# DA14580.net
KiCad netlist of a schematic drawn in Altium Designer
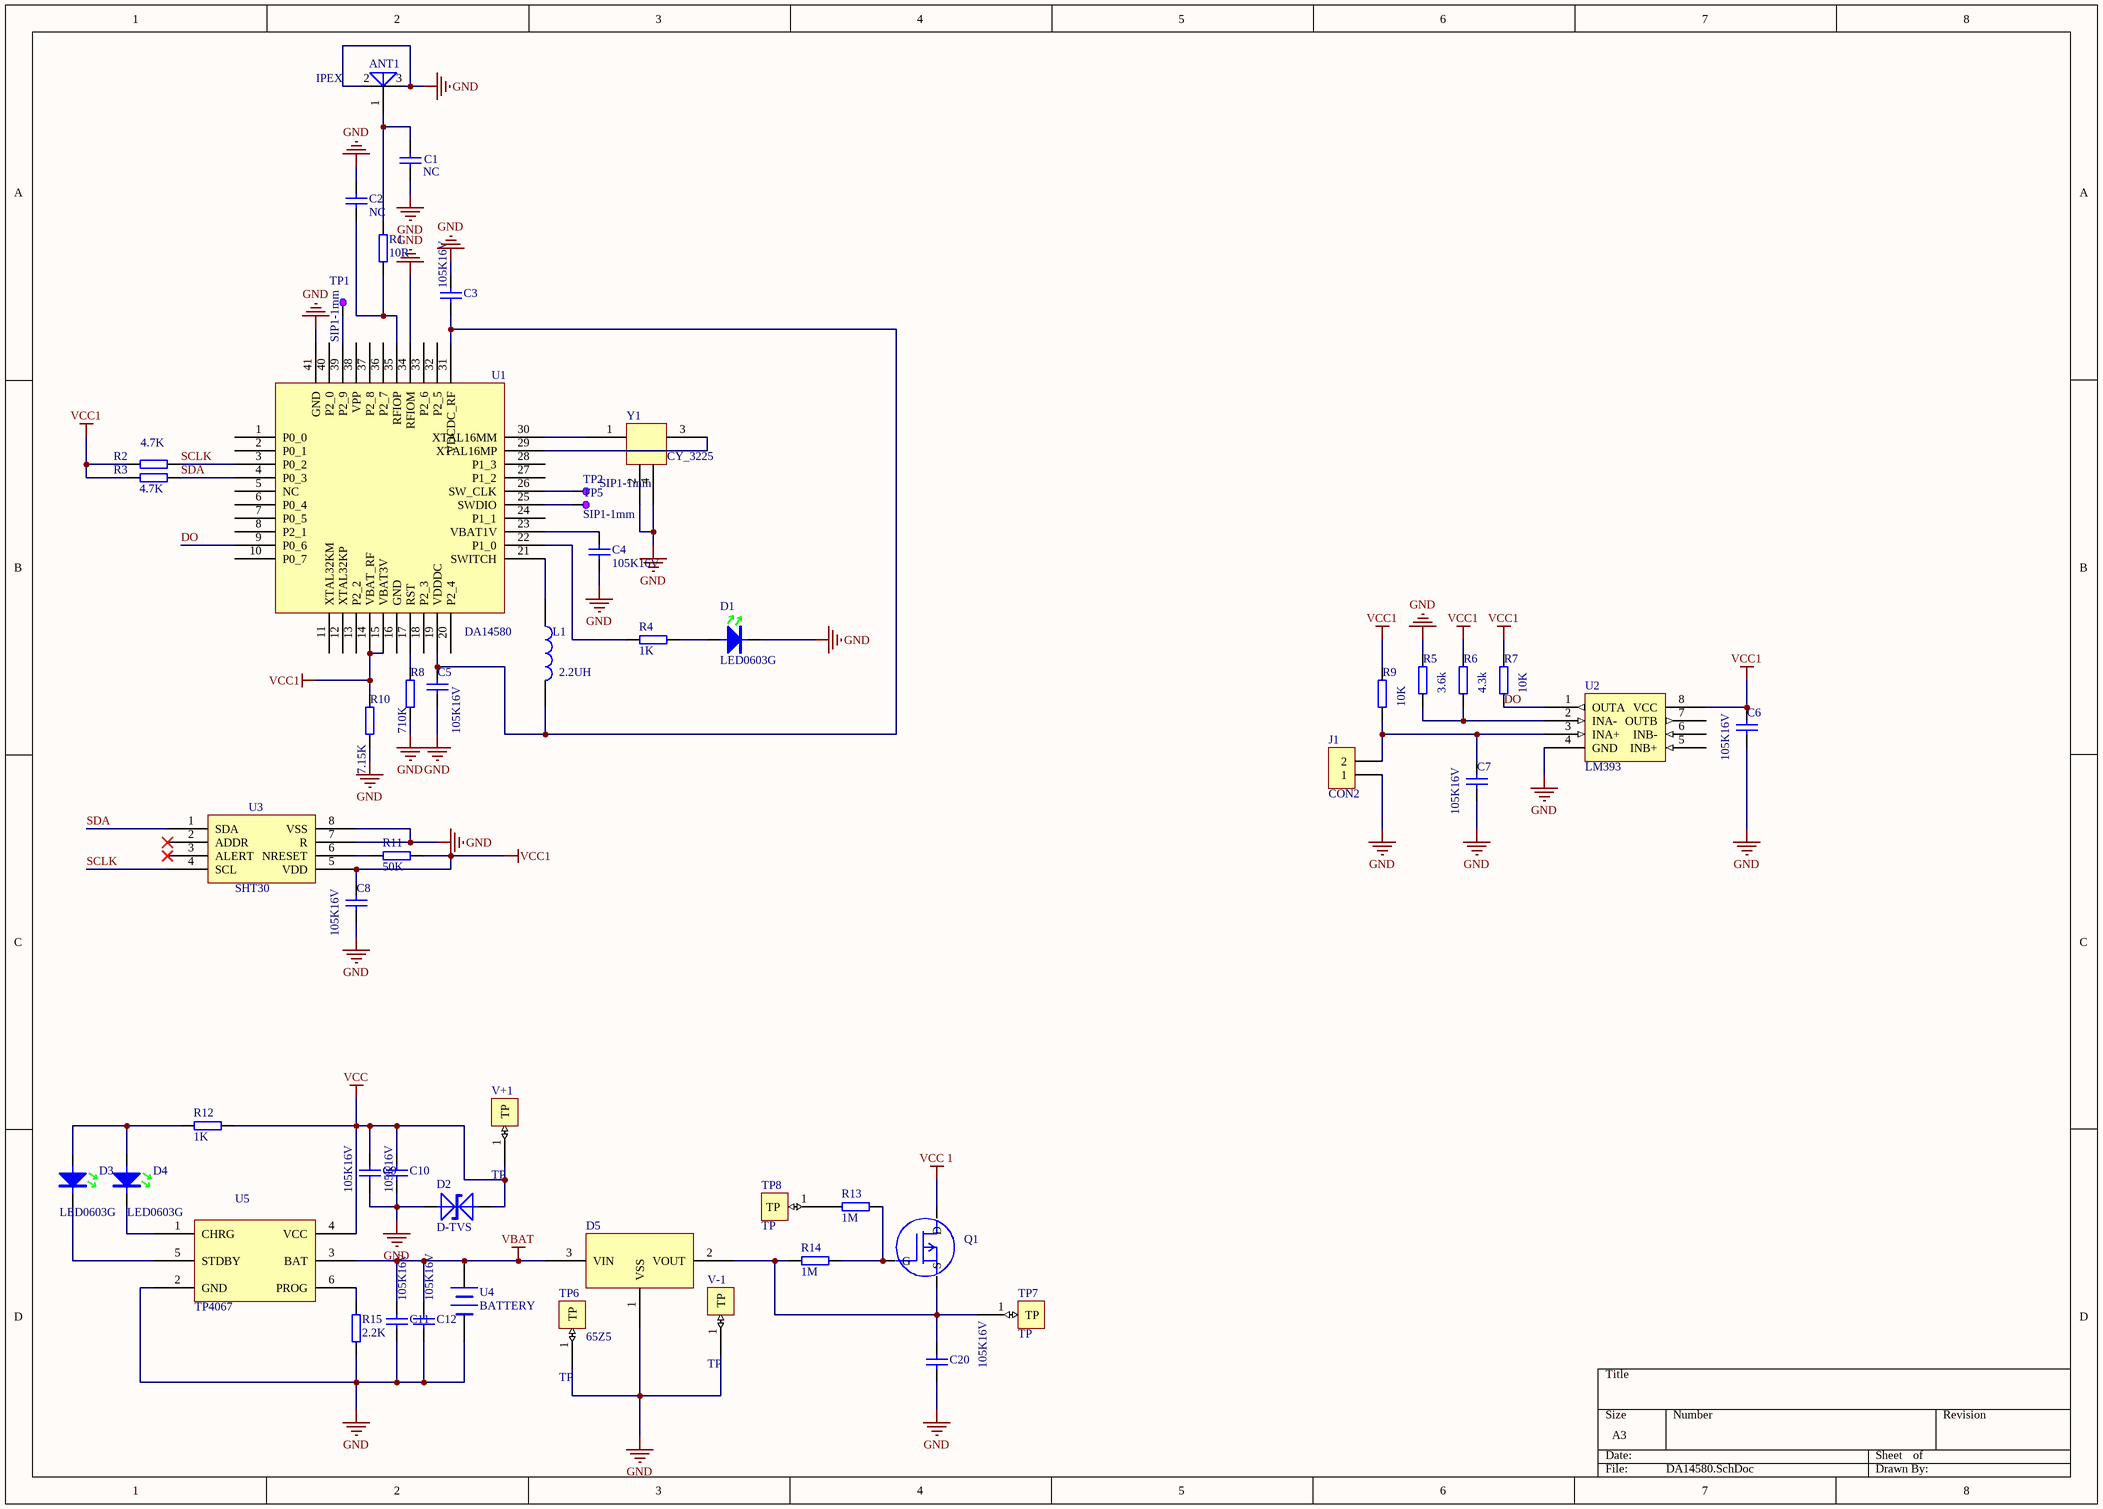
[diagram p0: DA14580.SchDoc]

(export (version "E")
  (design (tool "Eeschema 10.0.6"))
  (components
    (comp (ref "ANT1") (value "IPEX") (footprint "IFA") (libsource (lib "AIWAC-bolsterV01") (part "J-IPEX")))
    (comp (ref "C1")
      (value "NC")
      (footprint "C0402")
      (description "贴片电容-陶瓷")
      (libsource (lib "AIWAC-bolsterV01") (part "C0402X7R-101J10V"))
    )
    (comp (ref "C2")
      (value "NC")
      (footprint "C0402")
      (description "贴片电容-陶瓷")
      (libsource (lib "AIWAC-bolsterV01") (part "C0402X7R-101J10V"))
    )
    (comp (ref "C3")
      (value "105K16V")
      (footprint "C0603")
      (description "贴片电容-陶瓷")
      (libsource (lib "AIWAC-bolsterV01") (part "C0603X7R-105K16V"))
    )
    (comp (ref "C4")
      (value "105K16V")
      (footprint "C0603")
      (description "贴片电容-陶瓷")
      (libsource (lib "AIWAC-bolsterV01") (part "C0603X7R-105K16V"))
    )
    (comp (ref "C5")
      (value "105K16V")
      (footprint "C0603")
      (description "贴片电容-陶瓷")
      (libsource (lib "AIWAC-bolsterV01") (part "C0603X7R-105K16V"))
    )
    (comp (ref "C6")
      (value "105K16V")
      (footprint "C0603")
      (description "贴片电容-陶瓷")
      (libsource (lib "AIWAC-bolsterV01") (part "C0603X7R-105K16V"))
    )
    (comp (ref "C7")
      (value "105K16V")
      (footprint "C0603")
      (description "贴片电容-陶瓷")
      (libsource (lib "AIWAC-bolsterV01") (part "C0603X7R-105K16V"))
    )
    (comp (ref "C8")
      (value "105K16V")
      (footprint "C0603")
      (description "贴片电容-陶瓷")
      (libsource (lib "AIWAC-bolsterV01") (part "C0603X7R-105K16V"))
    )
    (comp (ref "C9")
      (value "105K16V")
      (footprint "C0603")
      (description "贴片电容-陶瓷")
      (libsource (lib "AIWAC-bolsterV01") (part "C0603X7R-105K16V"))
    )
    (comp (ref "C10")
      (value "105K16V")
      (footprint "C0603")
      (description "贴片电容-陶瓷")
      (libsource (lib "AIWAC-bolsterV01") (part "C0603X7R-105K16V"))
    )
    (comp (ref "C11")
      (value "105K16V")
      (footprint "C0603")
      (description "贴片电容-陶瓷")
      (libsource (lib "AIWAC-bolsterV01") (part "C0603X7R-105K16V"))
    )
    (comp (ref "C12")
      (value "105K16V")
      (footprint "C0603")
      (description "贴片电容-陶瓷")
      (libsource (lib "AIWAC-bolsterV01") (part "C0603X7R-105K16V"))
    )
    (comp (ref "C20")
      (value "105K16V")
      (footprint "C0603")
      (description "贴片电容-陶瓷")
      (libsource (lib "AIWAC-bolsterV01") (part "C0603X7R-105K16V"))
    )
    (comp (ref "D1")
      (value "LED0603G")
      (footprint "HS_0603D")
      (description "贴片二极管-LED")
      (libsource (lib "AIWAC-bolsterV01") (part "DLED-0603-G"))
    )
    (comp (ref "D2") (value "D-TVS") (footprint "0603C") (libsource (lib "XU-GENARAL SCH") (part "D-TVS")))
    (comp (ref "D3")
      (value "LED0603G")
      (footprint "HS_0603D")
      (description "贴片二极管-LED")
      (libsource (lib "AIWAC-bolsterV01") (part "DLED-0603-G"))
    )
    (comp (ref "D4")
      (value "LED0603G")
      (footprint "HS_0603D")
      (description "贴片二极管-LED")
      (libsource (lib "AIWAC-bolsterV01") (part "DLED-0603-G"))
    )
    (comp (ref "D5") (value "65Z5") (libsource (lib "AIWAC-bolsterV01") (part "65Z5")))
    (comp (ref "J1")
      (value "CON2")
      (footprint "J-SH1.0-T-1-LT-2A")
      (description "Connector")
      (libsource (lib "AIWAC-bolsterV01") (part "CON2"))
    )
    (comp (ref "L1")
      (value "2.2UH")
      (footprint "0805")
      (libsource (lib "AIWAC-bolsterV01") (part "INDUCTOR"))
    )
    (comp (ref "Q1")
      (value "AO3401 SOT-23")
      (footprint "SOT23-AO3401")
      (description "MOS管")
      (libsource (lib "AIWAC-bolsterV01") (part "2321 SOT-23"))
    )
    (comp (ref "R1")
      (value "10R")
      (footprint "R0402")
      (description "贴片电阻-通用")
      (libsource (lib "AIWAC-bolsterV01") (part "R0402-1KF"))
    )
    (comp (ref "R2")
      (value "4.7K")
      (footprint "R0402")
      (description "贴片电阻-通用")
      (libsource (lib "AIWAC-bolsterV01") (part "R0402-1KF"))
    )
    (comp (ref "R3")
      (value "4.7K")
      (footprint "R0402")
      (description "贴片电阻-通用")
      (libsource (lib "AIWAC-bolsterV01") (part "R0402-1KF"))
    )
    (comp (ref "R4")
      (value "1K")
      (footprint "R0402")
      (description "贴片电阻-通用")
      (libsource (lib "AIWAC-bolsterV01") (part "R0402-1KF"))
    )
    (comp (ref "R5")
      (value "3.6k")
      (footprint "R0402")
      (description "贴片电阻-通用")
      (libsource (lib "AIWAC-bolsterV01") (part "R0402-1KF"))
    )
    (comp (ref "R6")
      (value "4.3k")
      (footprint "R0402")
      (description "贴片电阻-通用")
      (libsource (lib "AIWAC-bolsterV01") (part "R0402-1KF"))
    )
    (comp (ref "R7")
      (value "10K")
      (footprint "R0402")
      (description "贴片电阻-通用")
      (libsource (lib "AIWAC-bolsterV01") (part "R0402-1KF"))
    )
    (comp (ref "R8")
      (value "710K")
      (footprint "R0402")
      (description "贴片电阻-通用")
      (libsource (lib "AIWAC-bolsterV01") (part "R0402-1KF"))
    )
    (comp (ref "R9")
      (value "10K")
      (footprint "R0402")
      (description "贴片电阻-通用")
      (libsource (lib "AIWAC-bolsterV01") (part "R0402-1KF"))
    )
    (comp (ref "R10")
      (value "7.15K")
      (footprint "R0402")
      (description "贴片电阻-通用")
      (libsource (lib "AIWAC-bolsterV01") (part "R0402-1KF"))
    )
    (comp (ref "R11")
      (value "50K")
      (footprint "R0402")
      (description "贴片电阻-通用")
      (libsource (lib "AIWAC-bolsterV01") (part "R0402-1KF"))
    )
    (comp (ref "R12")
      (value "1K")
      (footprint "R0402")
      (description "贴片电阻-通用")
      (libsource (lib "AIWAC-bolsterV01") (part "R0402-1KF"))
    )
    (comp (ref "R13")
      (value "1M")
      (footprint "R0402")
      (description "贴片电阻-通用")
      (libsource (lib "AIWAC-bolsterV01") (part "R0402-1KF"))
    )
    (comp (ref "R14")
      (value "1M")
      (footprint "R0402")
      (description "贴片电阻-通用")
      (libsource (lib "AIWAC-bolsterV01") (part "R0402-1KF"))
    )
    (comp (ref "R15")
      (value "2.2K")
      (footprint "R0402")
      (description "贴片电阻-通用")
      (libsource (lib "AIWAC-bolsterV01") (part "R0402-1KF"))
    )
    (comp (ref "TP1")
      (value "SIP1-1mm")
      (footprint "SIP - 1MM")
      (libsource (lib "AIWAC-bolsterV01") (part "SIP1-2mm"))
    )
    (comp (ref "TP2")
      (value "SIP1-1mm")
      (footprint "SIP - 1MM")
      (libsource (lib "AIWAC-bolsterV01") (part "SIP1-2mm"))
    )
    (comp (ref "TP5")
      (value "SIP1-1mm")
      (footprint "SIP - 1MM")
      (libsource (lib "AIWAC-bolsterV01") (part "SIP1-2mm"))
    )
    (comp (ref "TP6") (value "TP") (footprint "SIP-2MM") (libsource (lib "AIWAC-bolsterV01") (part "TP")))
    (comp (ref "TP7") (value "TP") (footprint "SIP-2MM") (libsource (lib "") (part "TP_1")))
    (comp (ref "TP8") (value "TP") (footprint "SIP-2MM") (libsource (lib "") (part "TP_2")))
    (comp (ref "U1")
      (value "DA14580")
      (footprint "QFN40P500*500_HS-41N")
      (description "bluetooth")
      (libsource (lib "AIWAC-bolsterV01") (part "DA14580"))
    )
    (comp (ref "U2") (value "LM393") (footprint "SO-8S") (libsource (lib "AIWAC-bolsterV01") (part "LM393")))
    (comp (ref "U3")
      (value "SHT30")
      (footprint "SHT30 DL7DV9")
      (libsource (lib "AIWAC-bolsterV01") (part "SHT30"))
    )
    (comp (ref "U4")
      (value "BATTERY")
      (footprint "BAT 4mm")
      (libsource (lib "HSC32K1(QFN56)_BlueTooth_V2.0_20171108 - 副本") (part "BATTERY"))
    )
    (comp (ref "U5")
      (value "TP4067")
      (footprint "SOT23-6")
      (libsource (lib "AIWAC-bolsterV01") (part "TP4067"))
    )
    (comp (ref "V+1") (value "TP") (footprint "SIP-2MM") (libsource (lib "AIWAC-bolsterV01") (part "TP")))
    (comp (ref "V-1") (value "TP") (footprint "SIP-2MM") (libsource (lib "AIWAC-bolsterV01") (part "TP")))
    (comp (ref "Y1")
      (value "CY_3225")
      (footprint "CY_3225")
      (libsource (lib "AIWAC-bolsterV01") (part "CY_3225"))
    )
  )
  (nets
    (net (code "1") (name "/DO") (class "Default")
      (node (ref "R7") (pin "1") (pinfunction "1_1") (pintype "passive"))
      (node (ref "U1") (pin "9") (pinfunction "P0_6_9") (pintype "passive"))
      (node (ref "U2") (pin "1") (pinfunction "OUTA_1") (pintype "output"))
    )
    (net (code "2") (name "/SCLK") (class "Default")
      (node (ref "R2") (pin "1") (pinfunction "1_1") (pintype "passive"))
      (node (ref "U1") (pin "3") (pinfunction "P0_2_3") (pintype "passive"))
      (node (ref "U3") (pin "4") (pinfunction "SCL_4") (pintype "passive"))
    )
    (net (code "3") (name "/SDA") (class "Default")
      (node (ref "R3") (pin "1") (pinfunction "1_1") (pintype "passive"))
      (node (ref "U1") (pin "4") (pinfunction "P0_3_4") (pintype "passive"))
      (node (ref "U3") (pin "1") (pinfunction "SDA_1") (pintype "passive"))
    )
    (net (code "4") (name "GND") (class "Default")
      (node (ref "ANT1") (pin "2") (pinfunction "2_2") (pintype "passive"))
      (node (ref "ANT1") (pin "3") (pinfunction "3_3") (pintype "passive"))
      (node (ref "C1") (pin "2") (pinfunction "2_2") (pintype "passive"))
      (node (ref "C10") (pin "2") (pinfunction "2_2") (pintype "passive"))
      (node (ref "C11") (pin "2") (pinfunction "2_2") (pintype "passive"))
      (node (ref "C12") (pin "2") (pinfunction "2_2") (pintype "passive"))
      (node (ref "C2") (pin "1") (pinfunction "1_1") (pintype "passive"))
      (node (ref "C20") (pin "2") (pinfunction "2_2") (pintype "passive"))
      (node (ref "C3") (pin "1") (pinfunction "1_1") (pintype "passive"))
      (node (ref "C4") (pin "2") (pinfunction "2_2") (pintype "passive"))
      (node (ref "C5") (pin "2") (pinfunction "2_2") (pintype "passive"))
      (node (ref "C6") (pin "2") (pinfunction "2_2") (pintype "passive"))
      (node (ref "C7") (pin "2") (pinfunction "2_2") (pintype "passive"))
      (node (ref "C8") (pin "2") (pinfunction "2_2") (pintype "passive"))
      (node (ref "C9") (pin "2") (pinfunction "2_2") (pintype "passive"))
      (node (ref "D1") (pin "2") (pinfunction "2_2") (pintype "passive"))
      (node (ref "D2") (pin "2") (pintype "passive"))
      (node (ref "D5") (pin "1") (pinfunction "VSS_1") (pintype "passive"))
      (node (ref "J1") (pin "1") (pinfunction "1_1") (pintype "passive"))
      (node (ref "R10") (pin "1") (pinfunction "1_1") (pintype "passive"))
      (node (ref "R15") (pin "1") (pinfunction "1_1") (pintype "passive"))
      (node (ref "R5") (pin "2") (pinfunction "2_2") (pintype "passive"))
      (node (ref "R8") (pin "1") (pinfunction "1_1") (pintype "passive"))
      (node (ref "TP6") (pin "1") (pinfunction "TP_1") (pintype "bidirectional"))
      (node (ref "U1") (pin "34") (pinfunction "RFIOM_34") (pintype "passive"))
      (node (ref "U1") (pin "41") (pinfunction "GND_41") (pintype "passive"))
      (node (ref "U2") (pin "4") (pinfunction "GND_4") (pintype "power_in"))
      (node (ref "U3") (pin "7") (pinfunction "R_7") (pintype "passive"))
      (node (ref "U3") (pin "8") (pinfunction "VSS_8") (pintype "passive"))
      (node (ref "U4") (pin "2") (pinfunction "-_2") (pintype "passive"))
      (node (ref "U5") (pin "2") (pinfunction "GND_2") (pintype "passive"))
      (node (ref "V-1") (pin "1") (pinfunction "TP_1") (pintype "bidirectional"))
      (node (ref "Y1") (pin "2") (pinfunction "2_2") (pintype "power_in"))
      (node (ref "Y1") (pin "4") (pinfunction "4_4") (pintype "power_in"))
    )
    (net (code "5") (name "Net-(ANT1-W)") (class "Default")
      (node (ref "ANT1") (pin "1") (pinfunction "W_1") (pintype "passive"))
      (node (ref "C1") (pin "1") (pinfunction "1_1") (pintype "passive"))
      (node (ref "R1") (pin "1") (pinfunction "1_1") (pintype "passive"))
    )
    (net (code "6") (name "Net-(D1-Pad1)") (class "Default")
      (node (ref "D1") (pin "1") (pinfunction "1_1") (pintype "passive"))
      (node (ref "R4") (pin "2") (pinfunction "2_2") (pintype "passive"))
    )
    (net (code "7") (name "Net-(D3-Pad1)") (class "Default")
      (node (ref "D3") (pin "1") (pinfunction "1_1") (pintype "passive"))
      (node (ref "D4") (pin "1") (pinfunction "1_1") (pintype "passive"))
      (node (ref "R12") (pin "1") (pinfunction "1_1") (pintype "passive"))
    )
    (net (code "8") (name "Net-(D5-VOUT)") (class "Default")
      (node (ref "C20") (pin "1") (pinfunction "1_1") (pintype "passive"))
      (node (ref "D5") (pin "2") (pinfunction "VOUT_2") (pintype "passive"))
      (node (ref "Q1") (pin "S") (pinfunction "S_S") (pintype "passive"))
      (node (ref "R14") (pin "1") (pinfunction "1_1") (pintype "passive"))
      (node (ref "TP7") (pin "1") (pinfunction "TP_1") (pintype "bidirectional"))
    )
    (net (code "9") (name "Net-(Q1-PadG)") (class "Default")
      (node (ref "Q1") (pin "G") (pinfunction "G_G") (pintype "passive"))
      (node (ref "R13") (pin "2") (pinfunction "2_2") (pintype "passive"))
      (node (ref "R14") (pin "2") (pinfunction "2_2") (pintype "passive"))
    )
    (net (code "10") (name "Net-(TP8-TP)") (class "Default")
      (node (ref "R13") (pin "1") (pinfunction "1_1") (pintype "passive"))
      (node (ref "TP8") (pin "1") (pinfunction "TP_1") (pintype "bidirectional"))
    )
    (net (code "11") (name "Net-(U1-P1_0)") (class "Default")
      (node (ref "R4") (pin "1") (pinfunction "1_1") (pintype "passive"))
      (node (ref "U1") (pin "22") (pinfunction "P1_0_22") (pintype "passive"))
    )
    (net (code "12") (name "Net-(U1-P2_9)") (class "Default")
      (node (ref "TP1") (pin "1") (pinfunction "1_1") (pintype "passive"))
      (node (ref "U1") (pin "39") (pinfunction "P2_9_39") (pintype "passive"))
    )
    (net (code "13") (name "Net-(U1-RFIOP)") (class "Default")
      (node (ref "C2") (pin "2") (pinfunction "2_2") (pintype "passive"))
      (node (ref "R1") (pin "2") (pinfunction "2_2") (pintype "passive"))
      (node (ref "U1") (pin "35") (pinfunction "RFIOP_35") (pintype "passive"))
    )
    (net (code "14") (name "Net-(U1-RST)") (class "Default")
      (node (ref "R8") (pin "2") (pinfunction "2_2") (pintype "passive"))
      (node (ref "U1") (pin "17") (pinfunction "RST_17") (pintype "passive"))
    )
    (net (code "15") (name "Net-(U1-SWDIO)") (class "Default")
      (node (ref "TP5") (pin "1") (pinfunction "1_1") (pintype "passive"))
      (node (ref "U1") (pin "25") (pinfunction "SWDIO_25") (pintype "passive"))
    )
    (net (code "16") (name "Net-(U1-SWITCH)") (class "Default")
      (node (ref "L1") (pin "1") (pinfunction "1_1") (pintype "passive"))
      (node (ref "U1") (pin "21") (pinfunction "SWITCH_21") (pintype "passive"))
    )
    (net (code "17") (name "Net-(U1-SW_CLK)") (class "Default")
      (node (ref "TP2") (pin "1") (pinfunction "1_1") (pintype "passive"))
      (node (ref "U1") (pin "26") (pinfunction "SW_CLK_26") (pintype "passive"))
    )
    (net (code "18") (name "Net-(U1-VBAT1V)") (class "Default")
      (node (ref "C4") (pin "1") (pinfunction "1_1") (pintype "passive"))
      (node (ref "U1") (pin "23") (pinfunction "VBAT1V_23") (pintype "passive"))
    )
    (net (code "19") (name "Net-(U1-VDCDC_RF)") (class "Default")
      (node (ref "C3") (pin "2") (pinfunction "2_2") (pintype "passive"))
      (node (ref "C5") (pin "1") (pinfunction "1_1") (pintype "passive"))
      (node (ref "L1") (pin "2") (pinfunction "2_2") (pintype "passive"))
      (node (ref "U1") (pin "19") (pinfunction "VDDDC_19") (pintype "passive"))
      (node (ref "U1") (pin "31") (pinfunction "VDCDC_RF_31") (pintype "passive"))
    )
    (net (code "20") (name "Net-(U1-XTAL16MM)") (class "Default")
      (node (ref "U1") (pin "30") (pinfunction "XTAL16MM_30") (pintype "passive"))
      (node (ref "Y1") (pin "1") (pinfunction "1_1") (pintype "power_in"))
    )
    (net (code "21") (name "Net-(U1-XTAL16MP)") (class "Default")
      (node (ref "U1") (pin "29") (pinfunction "XTAL16MP_29") (pintype "passive"))
      (node (ref "Y1") (pin "3") (pinfunction "3_3") (pintype "power_in"))
    )
    (net (code "22") (name "Net-(U2-INA+)") (class "Default")
      (node (ref "C7") (pin "1") (pinfunction "1_1") (pintype "passive"))
      (node (ref "J1") (pin "2") (pinfunction "2_2") (pintype "passive"))
      (node (ref "R9") (pin "1") (pinfunction "1_1") (pintype "passive"))
      (node (ref "U2") (pin "3") (pinfunction "INA+_3") (pintype "input"))
    )
    (net (code "23") (name "Net-(U2-INA-)") (class "Default")
      (node (ref "R5") (pin "1") (pinfunction "1_1") (pintype "passive"))
      (node (ref "R6") (pin "1") (pinfunction "1_1") (pintype "passive"))
      (node (ref "U2") (pin "2") (pinfunction "INA-_2") (pintype "input"))
    )
    (net (code "24") (name "Net-(U3-NRESET)") (class "Default")
      (node (ref "R11") (pin "1") (pinfunction "1_1") (pintype "passive"))
      (node (ref "U3") (pin "6") (pinfunction "NRESET_6") (pintype "passive"))
    )
    (net (code "25") (name "Net-(U5-CHRG)") (class "Default")
      (node (ref "D4") (pin "2") (pinfunction "2_2") (pintype "passive"))
      (node (ref "U5") (pin "1") (pinfunction "CHRG_1") (pintype "passive"))
    )
    (net (code "26") (name "Net-(U5-PROG)") (class "Default")
      (node (ref "R15") (pin "2") (pinfunction "2_2") (pintype "passive"))
      (node (ref "U5") (pin "6") (pinfunction "PROG_6") (pintype "passive"))
    )
    (net (code "27") (name "Net-(U5-STDBY)") (class "Default")
      (node (ref "D3") (pin "2") (pinfunction "2_2") (pintype "passive"))
      (node (ref "U5") (pin "5") (pinfunction "STDBY_5") (pintype "passive"))
    )
    (net (code "28") (name "VBAT") (class "Default")
      (node (ref "C11") (pin "1") (pinfunction "1_1") (pintype "passive"))
      (node (ref "C12") (pin "1") (pinfunction "1_1") (pintype "passive"))
      (node (ref "D5") (pin "3") (pinfunction "VIN_3") (pintype "passive"))
      (node (ref "U4") (pin "1") (pinfunction "+_1") (pintype "passive"))
      (node (ref "U5") (pin "3") (pinfunction "BAT_3") (pintype "passive"))
    )
    (net (code "29") (name "VCC") (class "Default")
      (node (ref "C10") (pin "1") (pinfunction "1_1") (pintype "passive"))
      (node (ref "C9") (pin "1") (pinfunction "1_1") (pintype "passive"))
      (node (ref "D2") (pin "1") (pintype "passive"))
      (node (ref "R12") (pin "2") (pinfunction "2_2") (pintype "passive"))
      (node (ref "U5") (pin "4") (pinfunction "VCC_4") (pintype "passive"))
      (node (ref "V+1") (pin "1") (pinfunction "TP_1") (pintype "bidirectional"))
    )
    (net (code "30") (name "VCC 1") (class "Default")
      (node (ref "Q1") (pin "D") (pinfunction "D_D") (pintype "passive"))
    )
    (net (code "31") (name "VCC1") (class "Default")
      (node (ref "C6") (pin "1") (pinfunction "1_1") (pintype "passive"))
      (node (ref "C8") (pin "1") (pinfunction "1_1") (pintype "passive"))
      (node (ref "R10") (pin "2") (pinfunction "2_2") (pintype "passive"))
      (node (ref "R11") (pin "2") (pinfunction "2_2") (pintype "passive"))
      (node (ref "R2") (pin "2") (pinfunction "2_2") (pintype "passive"))
      (node (ref "R3") (pin "2") (pinfunction "2_2") (pintype "passive"))
      (node (ref "R6") (pin "2") (pinfunction "2_2") (pintype "passive"))
      (node (ref "R7") (pin "2") (pinfunction "2_2") (pintype "passive"))
      (node (ref "R9") (pin "2") (pinfunction "2_2") (pintype "passive"))
      (node (ref "U1") (pin "14") (pinfunction "VBAT_RF_14") (pintype "passive"))
      (node (ref "U1") (pin "15") (pinfunction "VBAT3V_15") (pintype "passive"))
      (node (ref "U2") (pin "8") (pinfunction "VCC_8") (pintype "power_in"))
      (node (ref "U3") (pin "5") (pinfunction "VDD_5") (pintype "passive"))
    )
    (net (code "32") (name "unconnected-(U1-GND-Pad16)") (class "Default")
      (node (ref "U1") (pin "16") (pinfunction "GND_16") (pintype "passive"))
    )
    (net (code "33") (name "unconnected-(U1-NC-Pad5)") (class "Default")
      (node (ref "U1") (pin "5") (pinfunction "NC_5") (pintype "passive"))
    )
    (net (code "34") (name "unconnected-(U1-P0_0-Pad1)") (class "Default")
      (node (ref "U1") (pin "1") (pinfunction "P0_0_1") (pintype "passive"))
    )
    (net (code "35") (name "unconnected-(U1-P0_1-Pad2)") (class "Default")
      (node (ref "U1") (pin "2") (pinfunction "P0_1_2") (pintype "passive"))
    )
    (net (code "36") (name "unconnected-(U1-P0_4-Pad6)") (class "Default")
      (node (ref "U1") (pin "6") (pinfunction "P0_4_6") (pintype "passive"))
    )
    (net (code "37") (name "unconnected-(U1-P0_5-Pad7)") (class "Default")
      (node (ref "U1") (pin "7") (pinfunction "P0_5_7") (pintype "passive"))
    )
    (net (code "38") (name "unconnected-(U1-P0_7-Pad10)") (class "Default")
      (node (ref "U1") (pin "10") (pinfunction "P0_7_10") (pintype "passive"))
    )
    (net (code "39") (name "unconnected-(U1-P1_1-Pad24)") (class "Default")
      (node (ref "U1") (pin "24") (pinfunction "P1_1_24") (pintype "passive"))
    )
    (net (code "40") (name "unconnected-(U1-P1_2-Pad27)") (class "Default")
      (node (ref "U1") (pin "27") (pinfunction "P1_2_27") (pintype "passive"))
    )
    (net (code "41") (name "unconnected-(U1-P1_3-Pad28)") (class "Default")
      (node (ref "U1") (pin "28") (pinfunction "P1_3_28") (pintype "passive"))
    )
    (net (code "42") (name "unconnected-(U1-P2_0-Pad40)") (class "Default")
      (node (ref "U1") (pin "40") (pinfunction "P2_0_40") (pintype "passive"))
    )
    (net (code "43") (name "unconnected-(U1-P2_1-Pad8)") (class "Default")
      (node (ref "U1") (pin "8") (pinfunction "P2_1_8") (pintype "passive"))
    )
    (net (code "44") (name "unconnected-(U1-P2_2-Pad13)") (class "Default")
      (node (ref "U1") (pin "13") (pinfunction "P2_2_13") (pintype "passive"))
    )
    (net (code "45") (name "unconnected-(U1-P2_3-Pad18)") (class "Default")
      (node (ref "U1") (pin "18") (pinfunction "P2_3_18") (pintype "passive"))
    )
    (net (code "46") (name "unconnected-(U1-P2_4-Pad20)") (class "Default")
      (node (ref "U1") (pin "20") (pinfunction "P2_4_20") (pintype "passive"))
    )
    (net (code "47") (name "unconnected-(U1-P2_5-Pad32)") (class "Default")
      (node (ref "U1") (pin "32") (pinfunction "P2_5_32") (pintype "passive"))
    )
    (net (code "48") (name "unconnected-(U1-P2_6-Pad33)") (class "Default")
      (node (ref "U1") (pin "33") (pinfunction "P2_6_33") (pintype "passive"))
    )
    (net (code "49") (name "unconnected-(U1-P2_7-Pad36)") (class "Default")
      (node (ref "U1") (pin "36") (pinfunction "P2_7_36") (pintype "passive"))
    )
    (net (code "50") (name "unconnected-(U1-P2_8-Pad37)") (class "Default")
      (node (ref "U1") (pin "37") (pinfunction "P2_8_37") (pintype "passive"))
    )
    (net (code "51") (name "unconnected-(U1-VPP-Pad38)") (class "Default")
      (node (ref "U1") (pin "38") (pinfunction "VPP_38") (pintype "passive"))
    )
    (net (code "52") (name "unconnected-(U1-XTAL32KM-Pad11)") (class "Default")
      (node (ref "U1") (pin "11") (pinfunction "XTAL32KM_11") (pintype "passive"))
    )
    (net (code "53") (name "unconnected-(U1-XTAL32KP-Pad12)") (class "Default")
      (node (ref "U1") (pin "12") (pinfunction "XTAL32KP_12") (pintype "passive"))
    )
    (net (code "54") (name "unconnected-(U2-INB+-Pad5)") (class "Default")
      (node (ref "U2") (pin "5") (pinfunction "INB+_5") (pintype "input"))
    )
    (net (code "55") (name "unconnected-(U2-INB--Pad6)") (class "Default")
      (node (ref "U2") (pin "6") (pinfunction "INB-_6") (pintype "input"))
    )
    (net (code "56") (name "unconnected-(U2-OUTB-Pad7)") (class "Default")
      (node (ref "U2") (pin "7") (pinfunction "OUTB_7") (pintype "output"))
    )
    (net (code "57") (name "unconnected-(U3-ADDR-Pad2)") (class "Default")
      (node (ref "U3") (pin "2") (pinfunction "ADDR_2") (pintype "passive+no_connect"))
    )
    (net (code "58") (name "unconnected-(U3-ALERT-Pad3)") (class "Default")
      (node (ref "U3") (pin "3") (pinfunction "ALERT_3") (pintype "passive+no_connect"))
    )
  )
)
